# PROGRAMMING.net
KiCad netlist of a schematic drawn in Altium Designer
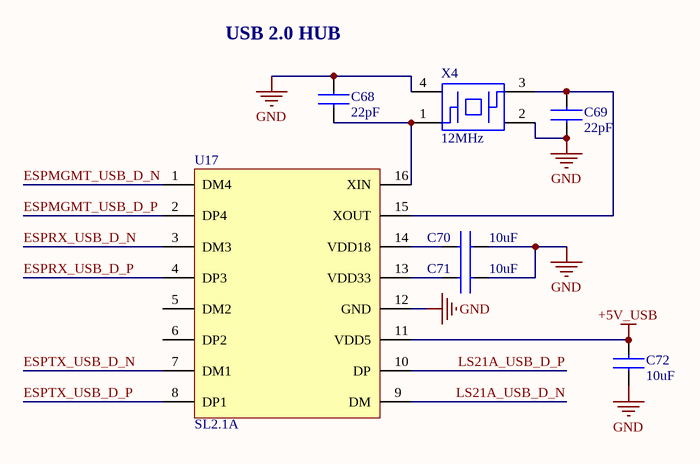
[diagram p0: PROGRAMMING.SchDoc]

(export (version "E")
  (design (tool "Eeschema 10.0.6"))
  (components
    (comp (ref "C68")
      (value "22pF")
      (footprint "CAP_0402")
      (description "MULTILAYER CERAMIC CAPACITORS MLCC - SMD/SMT 22PF 50V 0402 ROHS 0402CG220J500NT")
      (fields (field (name "MFR PART #") "0402CG220J500NT") (field (name "LCSC PART#") "C1555"))
      (libsource (lib "LotusSound") (part "CAP_0402CG220J500NT"))
    )
    (comp (ref "C69")
      (value "22pF")
      (footprint "CAP_0402")
      (description "MULTILAYER CERAMIC CAPACITORS MLCC - SMD/SMT 22PF 50V 0402 ROHS 0402CG220J500NT")
      (fields (field (name "MFR PART #") "0402CG220J500NT") (field (name "LCSC PART#") "C1555"))
      (libsource (lib "LotusSound") (part "CAP_0402CG220J500NT"))
    )
    (comp (ref "C70")
      (value "10uF")
      (footprint "CAP_0402")
      (description "Cap Ceramic 10uF 6.3V X5R 20% SMD 0402 85°C Paper T/R")
      (fields
        (field (name "MANUFACTURER") "Samsung")
        (field (name "MANUFACTURER PART NUMBER") "CL05A106MQ5NUNC")
      )
      (libsource (lib "LotusSound") (part "CAP_CL05A106MQ5NUNC"))
    )
    (comp (ref "C71")
      (value "10uF")
      (footprint "CAP_0402")
      (description "Cap Ceramic 10uF 6.3V X5R 20% SMD 0402 85°C Paper T/R")
      (fields
        (field (name "MANUFACTURER") "Samsung")
        (field (name "MANUFACTURER PART NUMBER") "CL05A106MQ5NUNC")
      )
      (libsource (lib "LotusSound") (part "CAP_CL05A106MQ5NUNC"))
    )
    (comp (ref "C72")
      (value "10uF")
      (footprint "CAP_0402")
      (description "Cap Ceramic 10uF 6.3V X5R 20% SMD 0402 85°C Paper T/R")
      (fields
        (field (name "MANUFACTURER") "Samsung")
        (field (name "MANUFACTURER PART NUMBER") "CL05A106MQ5NUNC")
      )
      (libsource (lib "LotusSound") (part "CAP_CL05A106MQ5NUNC"))
    )
    (comp (ref "U17")
      (value "SL2.1A")
      (footprint "IC_SL2.1A")
      (description "USB 2.0 HIGH SPEED 4-PORT HUB CONTROLLER")
      (fields (field (name "MF") "CoreChips ShenZhen CO.,Ltd"))
      (libsource (lib "LotusSound") (part "IC_SL2.1A"))
    )
    (comp (ref "X4")
      (value "12MHz")
      (footprint "XTAL_TAXM12M4RLBDDT2T")
      (fields
        (field (name "MANUFACTURER") "TAE(Zhejiang Abel Elec)")
        (field (name "MANUFACTURER PART NUMBER") "TAXM12M4RLBDDT2T")
      )
      (libsource (lib "LotusSound") (part "XTAL_TAXM12M4RLBDDT2T"))
    )
  )
  (nets
    (net (code "1") (name "+5V_USB") (class "Default")
      (node (ref "C72") (pin "2") (pinfunction "2_2") (pintype "passive"))
      (node (ref "U17") (pin "11") (pinfunction "VDD5_11") (pintype "passive"))
    )
    (net (code "2") (name "/ESPMGMT_USB_D_N") (class "Default")
      (node (ref "U17") (pin "1") (pinfunction "DM4_1") (pintype "passive"))
    )
    (net (code "3") (name "/ESPMGMT_USB_D_P") (class "Default")
      (node (ref "U17") (pin "2") (pinfunction "DP4_2") (pintype "passive"))
    )
    (net (code "4") (name "/ESPRX_USB_D_N") (class "Default")
      (node (ref "U17") (pin "3") (pinfunction "DM3_3") (pintype "passive"))
    )
    (net (code "5") (name "/ESPRX_USB_D_P") (class "Default")
      (node (ref "U17") (pin "4") (pinfunction "DP3_4") (pintype "passive"))
    )
    (net (code "6") (name "/ESPTX_USB_D_N") (class "Default")
      (node (ref "U17") (pin "7") (pinfunction "DM1_7") (pintype "passive"))
    )
    (net (code "7") (name "/ESPTX_USB_D_P") (class "Default")
      (node (ref "U17") (pin "8") (pinfunction "DP1_8") (pintype "passive"))
    )
    (net (code "8") (name "/LS21A_USB_D_N") (class "Default")
      (node (ref "U17") (pin "9") (pinfunction "DM_9") (pintype "passive"))
    )
    (net (code "9") (name "/LS21A_USB_D_P") (class "Default")
      (node (ref "U17") (pin "10") (pinfunction "DP_10") (pintype "passive"))
    )
    (net (code "10") (name "GND") (class "Default")
      (node (ref "C68") (pin "2") (pinfunction "2_2") (pintype "passive"))
      (node (ref "C69") (pin "1") (pinfunction "1_1") (pintype "passive"))
      (node (ref "C70") (pin "2") (pinfunction "2_2") (pintype "passive"))
      (node (ref "C71") (pin "2") (pinfunction "2_2") (pintype "passive"))
      (node (ref "C72") (pin "1") (pinfunction "1_1") (pintype "passive"))
      (node (ref "U17") (pin "12") (pinfunction "GND_12") (pintype "passive"))
      (node (ref "X4") (pin "2") (pinfunction "GND_2") (pintype "power_in"))
      (node (ref "X4") (pin "4") (pinfunction "4_4") (pintype "passive"))
    )
    (net (code "11") (name "Net-(U17-VDD18)") (class "Default")
      (node (ref "C70") (pin "1") (pinfunction "1_1") (pintype "passive"))
      (node (ref "U17") (pin "14") (pinfunction "VDD18_14") (pintype "passive"))
    )
    (net (code "12") (name "Net-(U17-VDD33)") (class "Default")
      (node (ref "C71") (pin "1") (pinfunction "1_1") (pintype "passive"))
      (node (ref "U17") (pin "13") (pinfunction "VDD33_13") (pintype "passive"))
    )
    (net (code "13") (name "Net-(U17-XIN)") (class "Default")
      (node (ref "C68") (pin "1") (pinfunction "1_1") (pintype "passive"))
      (node (ref "U17") (pin "16") (pinfunction "XIN_16") (pintype "passive"))
      (node (ref "X4") (pin "1") (pinfunction "IN/OUT_1") (pintype "passive"))
    )
    (net (code "14") (name "Net-(U17-XOUT)") (class "Default")
      (node (ref "C69") (pin "2") (pinfunction "2_2") (pintype "passive"))
      (node (ref "U17") (pin "15") (pinfunction "XOUT_15") (pintype "passive"))
      (node (ref "X4") (pin "3") (pinfunction "3_3") (pintype "passive"))
    )
    (net (code "15") (name "unconnected-(U17-DM2-Pad5)") (class "Default")
      (node (ref "U17") (pin "5") (pinfunction "DM2_5") (pintype "passive"))
    )
    (net (code "16") (name "unconnected-(U17-DP2-Pad6)") (class "Default")
      (node (ref "U17") (pin "6") (pinfunction "DP2_6") (pintype "passive"))
    )
  )
)
